# 1.net
KiCad netlist of a schematic drawn in EasyEDA
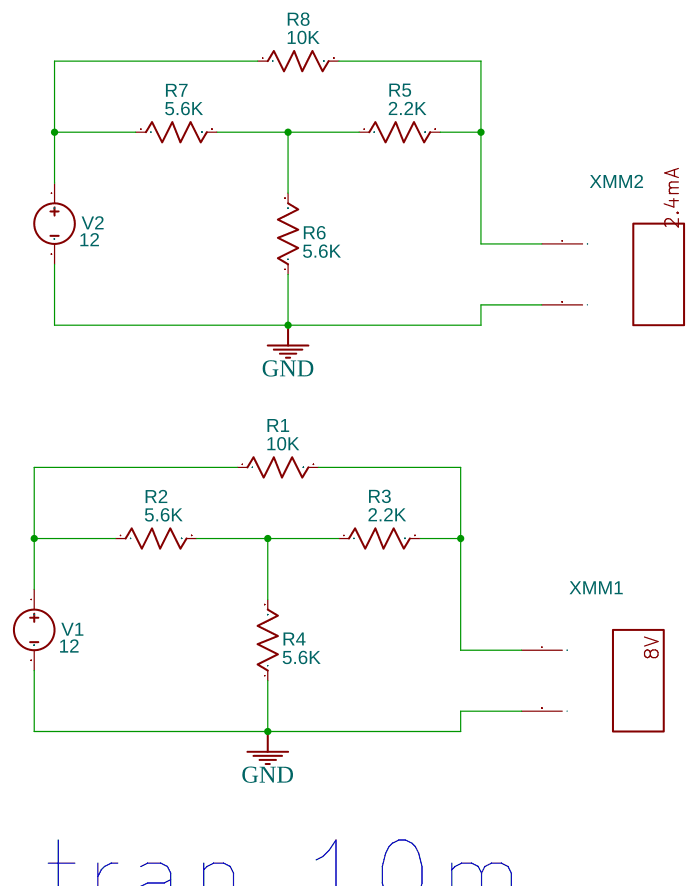
[diagram p0: schematic sheet]

(export (version "E")
  (design (tool "Eeschema 10.0.6"))
  (components
    (comp (ref "R1") (value "10K") (libsource (lib "") (part "Resistor_US")))
    (comp (ref "R2") (value "5.6K") (libsource (lib "") (part "Resistor_US")))
    (comp (ref "R3") (value "2.2K") (libsource (lib "") (part "Resistor_US")))
    (comp (ref "R4") (value "5.6K") (libsource (lib "") (part "Resistor_US_1")))
    (comp (ref "R5") (value "2.2K") (libsource (lib "") (part "Resistor_US")))
    (comp (ref "R6") (value "5.6K") (libsource (lib "") (part "Resistor_US_1")))
    (comp (ref "R7") (value "5.6K") (libsource (lib "") (part "Resistor_US")))
    (comp (ref "R8") (value "10K") (libsource (lib "") (part "Resistor_US")))
    (comp (ref "V1") (value "12") (libsource (lib "") (part "VDC")))
    (comp (ref "V2") (value "12") (libsource (lib "") (part "VDC")))
    (comp (ref "XMM1") (value "Multimeter") (libsource (lib "") (part "MULTIMETER")))
    (comp (ref "XMM2") (value "Multimeter") (libsource (lib "") (part "MULTIMETER_1")))
  )
  (nets
    (net (code "1") (name "GND") (class "Default")
      (node (ref "R4") (pin "1") (pinfunction "1_1") (pintype "unspecified"))
      (node (ref "R6") (pin "1") (pinfunction "1_1") (pintype "unspecified"))
      (node (ref "V1") (pin "2") (pinfunction "2_2") (pintype "unspecified"))
      (node (ref "V2") (pin "2") (pinfunction "2_2") (pintype "unspecified"))
      (node (ref "XMM1") (pin "2") (pinfunction "I_2") (pintype "unspecified"))
      (node (ref "XMM2") (pin "2") (pinfunction "I_2") (pintype "unspecified"))
    )
    (net (code "2") (name "Net-(R1-Pad1)") (class "Default")
      (node (ref "R1") (pin "1") (pinfunction "1_1") (pintype "unspecified"))
      (node (ref "R2") (pin "1") (pinfunction "1_1") (pintype "unspecified"))
      (node (ref "V1") (pin "1") (pinfunction "1_1") (pintype "unspecified"))
    )
    (net (code "3") (name "Net-(R2-Pad2)") (class "Default")
      (node (ref "R2") (pin "2") (pinfunction "2_2") (pintype "unspecified"))
      (node (ref "R3") (pin "1") (pinfunction "1_1") (pintype "unspecified"))
      (node (ref "R4") (pin "2") (pinfunction "2_2") (pintype "unspecified"))
    )
    (net (code "4") (name "Net-(R5-Pad1)") (class "Default")
      (node (ref "R5") (pin "1") (pinfunction "1_1") (pintype "unspecified"))
      (node (ref "R6") (pin "2") (pinfunction "2_2") (pintype "unspecified"))
      (node (ref "R7") (pin "2") (pinfunction "2_2") (pintype "unspecified"))
    )
    (net (code "5") (name "Net-(R7-Pad1)") (class "Default")
      (node (ref "R7") (pin "1") (pinfunction "1_1") (pintype "unspecified"))
      (node (ref "R8") (pin "1") (pinfunction "1_1") (pintype "unspecified"))
      (node (ref "V2") (pin "1") (pinfunction "1_1") (pintype "unspecified"))
    )
    (net (code "6") (name "Net-(XMM1-+)") (class "Default")
      (node (ref "R1") (pin "2") (pinfunction "2_2") (pintype "unspecified"))
      (node (ref "R3") (pin "2") (pinfunction "2_2") (pintype "unspecified"))
      (node (ref "XMM1") (pin "1") (pinfunction "+_1") (pintype "unspecified"))
    )
    (net (code "7") (name "Net-(XMM2-+)") (class "Default")
      (node (ref "R5") (pin "2") (pinfunction "2_2") (pintype "unspecified"))
      (node (ref "R8") (pin "2") (pinfunction "2_2") (pintype "unspecified"))
      (node (ref "XMM2") (pin "1") (pinfunction "+_1") (pintype "unspecified"))
    )
  )
)
